# SCH_Fermenter.net
KiCad netlist of a schematic drawn in EasyEDA
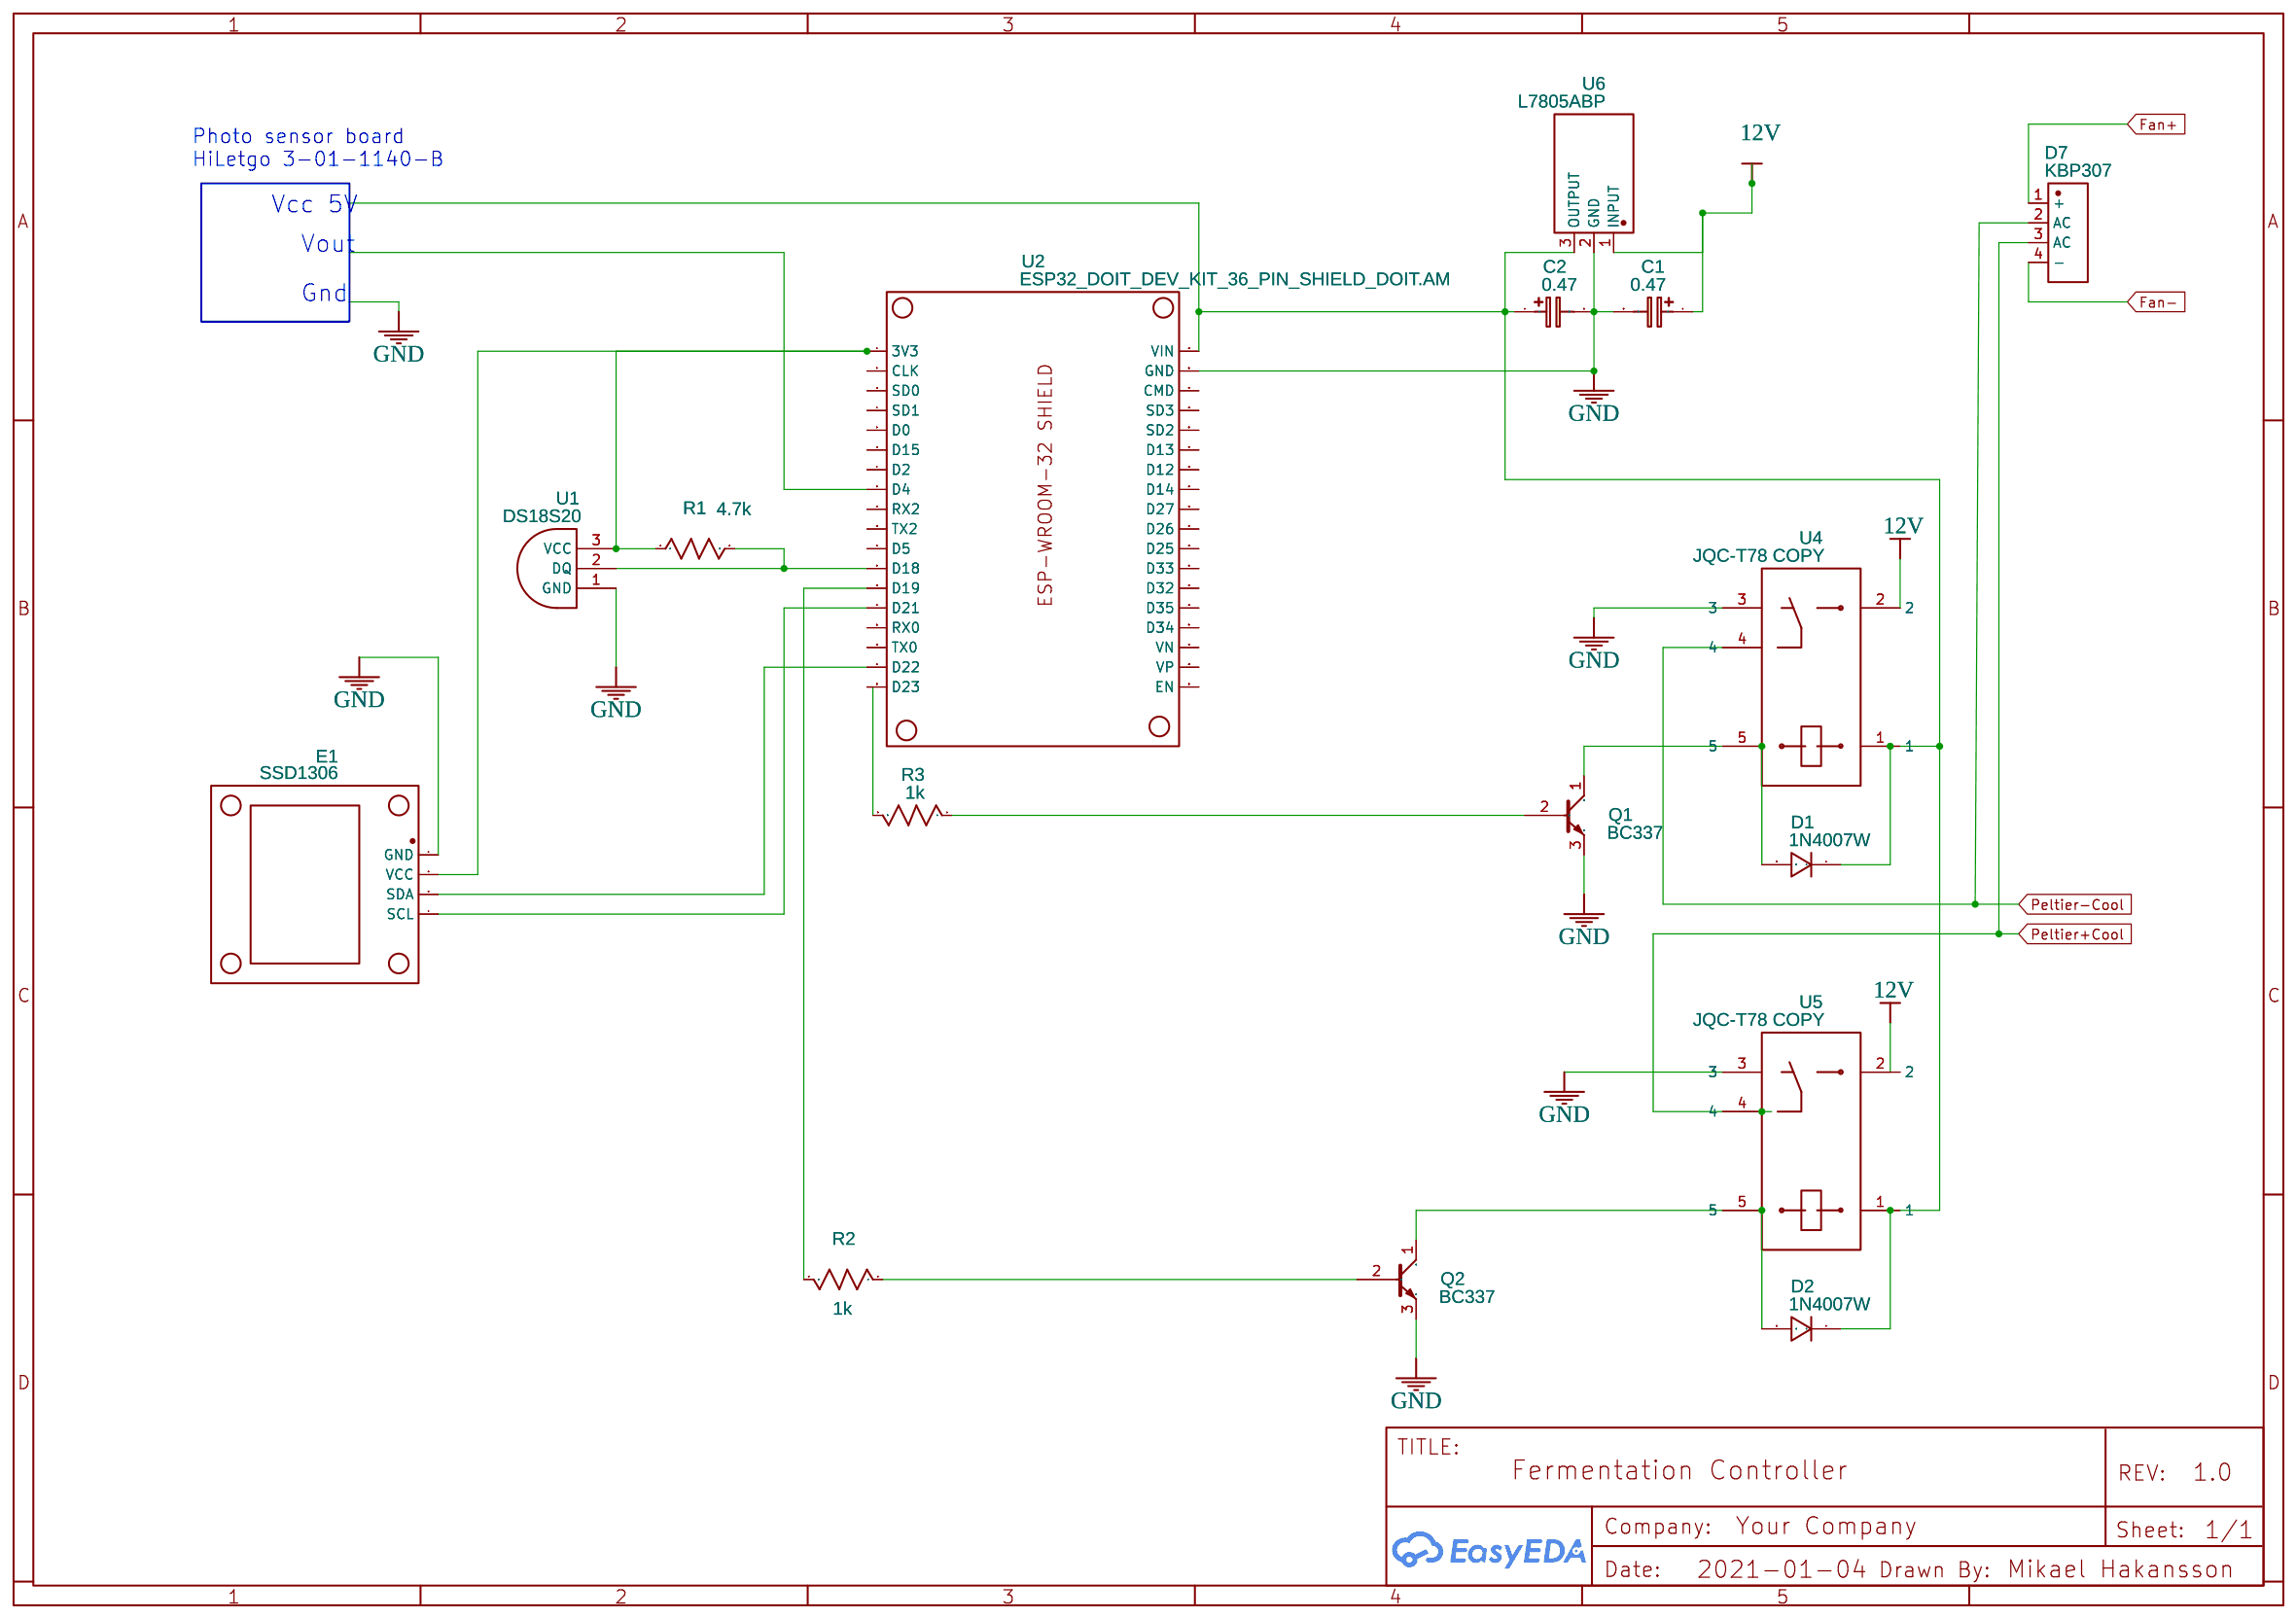
[diagram p0: schematic sheet]

(export (version "E")
  (design (tool "Eeschema 10.0.6"))
  (components
    (comp (ref "C1") (value "0.47") (libsource (lib "") (part "C_Tan_SMD_A_EU")))
    (comp (ref "C2") (value "0.47") (libsource (lib "") (part "C_Tan_SMD_A_EU_1")))
    (comp (ref "D1")
      (value "1N4007W")
      (fields (field (name "Manufacturer") "BLUE ROCKET"))
      (libsource (lib "") (part "1N4007W"))
    )
    (comp (ref "D2")
      (value "1N4007W")
      (fields (field (name "Manufacturer") "BLUE ROCKET"))
      (libsource (lib "") (part "1N4007W"))
    )
    (comp (ref "D7")
      (value "KBP307")
      (fields (field (name "Manufacturer") "MDD"))
      (libsource (lib "") (part "KBP307"))
    )
    (comp (ref "E1")
      (value "SSD1306")
      (fields (field (name "Manufacturer Part") "WJ2EDGVC-5.08-4P") (field (name "Manufacturer") "ReliaPro"))
      (libsource (lib "") (part "SSD1306"))
    )
    (comp (ref "Q1") (value "BC337") (libsource (lib "") (part "BC337")))
    (comp (ref "Q2") (value "BC337") (libsource (lib "") (part "BC337")))
    (comp (ref "R1") (value "4.7k") (libsource (lib "") (part "R_0603_US")))
    (comp (ref "R2") (value "1k") (libsource (lib "") (part "R_0603_US_1")))
    (comp (ref "R3") (value "1k") (libsource (lib "") (part "R_0603_US_1")))
    (comp (ref "U1")
      (value "DS18S20")
      (fields (field (name "Manufacturer") "MAXIM"))
      (libsource (lib "") (part "DS18S20"))
    )
    (comp (ref "U2")
      (value "ESP32_DOIT_DEV_KIT_36_PIN_SHIELD_DOIT.AM")
      (fields (field (name "Manufacturer Part") "ESP32_DOIT_DEVKIT_36_PIN"))
      (libsource (lib "") (part "ESP32_DOIT_DEV_KIT_36_PIN_SHIELD_DOIT.AM"))
    )
    (comp (ref "U4") (value "JQC-T78 COPY") (libsource (lib "") (part "JQC-T78 COPY")))
    (comp (ref "U5") (value "JQC-T78 COPY") (libsource (lib "") (part "JQC-T78 COPY")))
    (comp (ref "U6")
      (value "L7805ABP")
      (fields (field (name "Manufacturer") "ST(意法半导体)"))
      (libsource (lib "") (part "L7805ABP"))
    )
  )
  (nets
    (net (code "1") (name "12V") (class "Default")
      (node (ref "C1") (pin "1") (pinfunction "1_1") (pintype "unspecified"))
      (node (ref "U4") (pin "2") (pinfunction "2_2") (pintype "unspecified"))
      (node (ref "U5") (pin "2") (pinfunction "2_2") (pintype "unspecified"))
      (node (ref "U6") (pin "1") (pinfunction "INPUT_1") (pintype "unspecified"))
    )
    (net (code "2") (name "Fan+") (class "Default")
      (node (ref "D7") (pin "1") (pinfunction "+_1") (pintype "unspecified"))
    )
    (net (code "3") (name "Fan-") (class "Default")
      (node (ref "D7") (pin "4") (pinfunction "-_4") (pintype "unspecified"))
    )
    (net (code "4") (name "GND") (class "Default")
      (node (ref "C1") (pin "2") (pinfunction "2_2") (pintype "unspecified"))
      (node (ref "C2") (pin "2") (pinfunction "2_2") (pintype "unspecified"))
      (node (ref "E1") (pin "1") (pinfunction "GND_1") (pintype "unspecified"))
      (node (ref "Q1") (pin "3") (pinfunction "E_3") (pintype "unspecified"))
      (node (ref "Q2") (pin "3") (pinfunction "E_3") (pintype "unspecified"))
      (node (ref "U1") (pin "1") (pinfunction "GND_1") (pintype "unspecified"))
      (node (ref "U2") (pin "35") (pinfunction "GND_35") (pintype "input"))
      (node (ref "U4") (pin "3") (pinfunction "3_3") (pintype "unspecified"))
      (node (ref "U5") (pin "3") (pinfunction "3_3") (pintype "unspecified"))
      (node (ref "U6") (pin "2") (pinfunction "GND_2") (pintype "unspecified"))
    )
    (net (code "5") (name "Net-(E1-SCL)") (class "Default")
      (node (ref "E1") (pin "4") (pinfunction "SCL_4") (pintype "unspecified"))
      (node (ref "U2") (pin "14") (pinfunction "D21_14") (pintype "input"))
    )
    (net (code "6") (name "Net-(E1-SDA)") (class "Default")
      (node (ref "E1") (pin "3") (pinfunction "SDA_3") (pintype "unspecified"))
      (node (ref "U2") (pin "17") (pinfunction "D22_17") (pintype "input"))
    )
    (net (code "7") (name "Net-(E1-VCC)") (class "Default")
      (node (ref "E1") (pin "2") (pinfunction "VCC_2") (pintype "unspecified"))
      (node (ref "R1") (pin "1") (pinfunction "1_1") (pintype "unspecified"))
      (node (ref "U1") (pin "3") (pinfunction "VCC_3") (pintype "unspecified"))
      (node (ref "U2") (pin "1") (pinfunction "3V3_1") (pintype "input"))
    )
    (net (code "8") (name "Net-(Q1-B)") (class "Default")
      (node (ref "Q1") (pin "2") (pinfunction "B_2") (pintype "input"))
      (node (ref "R3") (pin "1") (pinfunction "1_1") (pintype "unspecified"))
    )
    (net (code "9") (name "Net-(Q1-C)") (class "Default")
      (node (ref "D1") (pin "2") (pinfunction "2_2") (pintype "unspecified"))
      (node (ref "Q1") (pin "1") (pinfunction "C_1") (pintype "unspecified"))
      (node (ref "U4") (pin "5") (pinfunction "5_5") (pintype "unspecified"))
    )
    (net (code "10") (name "Net-(Q2-B)") (class "Default")
      (node (ref "Q2") (pin "2") (pinfunction "B_2") (pintype "input"))
      (node (ref "R2") (pin "1") (pinfunction "1_1") (pintype "unspecified"))
    )
    (net (code "11") (name "Net-(Q2-C)") (class "Default")
      (node (ref "D2") (pin "2") (pinfunction "2_2") (pintype "unspecified"))
      (node (ref "Q2") (pin "1") (pinfunction "C_1") (pintype "unspecified"))
      (node (ref "U5") (pin "5") (pinfunction "5_5") (pintype "unspecified"))
    )
    (net (code "12") (name "Net-(U1-DQ)") (class "Default")
      (node (ref "R1") (pin "2") (pinfunction "2_2") (pintype "unspecified"))
      (node (ref "U1") (pin "2") (pinfunction "DQ_2") (pintype "unspecified"))
      (node (ref "U2") (pin "12") (pinfunction "D18_12") (pintype "input"))
    )
    (net (code "13") (name "Net-(U2-D19)") (class "Default")
      (node (ref "R2") (pin "2") (pinfunction "2_2") (pintype "unspecified"))
      (node (ref "U2") (pin "13") (pinfunction "D19_13") (pintype "input"))
    )
    (net (code "14") (name "Net-(U2-D23)") (class "Default")
      (node (ref "R3") (pin "2") (pinfunction "2_2") (pintype "unspecified"))
      (node (ref "U2") (pin "18") (pinfunction "D23_18") (pintype "input"))
    )
    (net (code "15") (name "Net-(U2-VIN)") (class "Default")
      (node (ref "C2") (pin "1") (pinfunction "1_1") (pintype "unspecified"))
      (node (ref "D1") (pin "1") (pinfunction "1_1") (pintype "unspecified"))
      (node (ref "D2") (pin "1") (pinfunction "1_1") (pintype "unspecified"))
      (node (ref "U2") (pin "36") (pinfunction "VIN_36") (pintype "input"))
      (node (ref "U4") (pin "1") (pinfunction "1_1") (pintype "unspecified"))
      (node (ref "U5") (pin "1") (pinfunction "1_1") (pintype "unspecified"))
      (node (ref "U6") (pin "3") (pinfunction "OUTPUT_3") (pintype "unspecified"))
    )
    (net (code "16") (name "Peltier+Cool") (class "Default")
      (node (ref "D7") (pin "3") (pinfunction "AC_3") (pintype "unspecified"))
      (node (ref "U5") (pin "4") (pinfunction "4_4") (pintype "unspecified"))
    )
    (net (code "17") (name "Peltier-Cool") (class "Default")
      (node (ref "D7") (pin "2") (pinfunction "AC_2") (pintype "unspecified"))
      (node (ref "U4") (pin "4") (pinfunction "4_4") (pintype "unspecified"))
    )
    (net (code "18") (name "unconnected-(U2-CLK-Pad2)") (class "Default")
      (node (ref "U2") (pin "2") (pinfunction "CLK_2") (pintype "input"))
    )
    (net (code "19") (name "unconnected-(U2-CMD-Pad34)") (class "Default")
      (node (ref "U2") (pin "34") (pinfunction "CMD_34") (pintype "input"))
    )
    (net (code "20") (name "unconnected-(U2-D0-Pad5)") (class "Default")
      (node (ref "U2") (pin "5") (pinfunction "D0_5") (pintype "input"))
    )
    (net (code "21") (name "unconnected-(U2-D2-Pad7)") (class "Default")
      (node (ref "U2") (pin "7") (pinfunction "D2_7") (pintype "input"))
    )
    (net (code "22") (name "unconnected-(U2-D4-Pad8)") (class "Default")
      (node (ref "U2") (pin "8") (pinfunction "D4_8") (pintype "input"))
    )
    (net (code "23") (name "unconnected-(U2-D5-Pad11)") (class "Default")
      (node (ref "U2") (pin "11") (pinfunction "D5_11") (pintype "input"))
    )
    (net (code "24") (name "unconnected-(U2-D12-Pad30)") (class "Default")
      (node (ref "U2") (pin "30") (pinfunction "D12_30") (pintype "input"))
    )
    (net (code "25") (name "unconnected-(U2-D13-Pad31)") (class "Default")
      (node (ref "U2") (pin "31") (pinfunction "D13_31") (pintype "input"))
    )
    (net (code "26") (name "unconnected-(U2-D14-Pad29)") (class "Default")
      (node (ref "U2") (pin "29") (pinfunction "D14_29") (pintype "input"))
    )
    (net (code "27") (name "unconnected-(U2-D15-Pad6)") (class "Default")
      (node (ref "U2") (pin "6") (pinfunction "D15_6") (pintype "input"))
    )
    (net (code "28") (name "unconnected-(U2-D25-Pad26)") (class "Default")
      (node (ref "U2") (pin "26") (pinfunction "D25_26") (pintype "input"))
    )
    (net (code "29") (name "unconnected-(U2-D26-Pad27)") (class "Default")
      (node (ref "U2") (pin "27") (pinfunction "D26_27") (pintype "input"))
    )
    (net (code "30") (name "unconnected-(U2-D27-Pad28)") (class "Default")
      (node (ref "U2") (pin "28") (pinfunction "D27_28") (pintype "input"))
    )
    (net (code "31") (name "unconnected-(U2-D32-Pad24)") (class "Default")
      (node (ref "U2") (pin "24") (pinfunction "D32_24") (pintype "input"))
    )
    (net (code "32") (name "unconnected-(U2-D33-Pad25)") (class "Default")
      (node (ref "U2") (pin "25") (pinfunction "D33_25") (pintype "input"))
    )
    (net (code "33") (name "unconnected-(U2-D34-Pad22)") (class "Default")
      (node (ref "U2") (pin "22") (pinfunction "D34_22") (pintype "input"))
    )
    (net (code "34") (name "unconnected-(U2-D35-Pad23)") (class "Default")
      (node (ref "U2") (pin "23") (pinfunction "D35_23") (pintype "input"))
    )
    (net (code "35") (name "unconnected-(U2-EN-Pad19)") (class "Default")
      (node (ref "U2") (pin "19") (pinfunction "EN_19") (pintype "input"))
    )
    (net (code "36") (name "unconnected-(U2-RX0-Pad15)") (class "Default")
      (node (ref "U2") (pin "15") (pinfunction "RX0_15") (pintype "input"))
    )
    (net (code "37") (name "unconnected-(U2-RX2-Pad9)") (class "Default")
      (node (ref "U2") (pin "9") (pinfunction "RX2_9") (pintype "input"))
    )
    (net (code "38") (name "unconnected-(U2-SD0-Pad3)") (class "Default")
      (node (ref "U2") (pin "3") (pinfunction "SD0_3") (pintype "input"))
    )
    (net (code "39") (name "unconnected-(U2-SD1-Pad4)") (class "Default")
      (node (ref "U2") (pin "4") (pinfunction "SD1_4") (pintype "input"))
    )
    (net (code "40") (name "unconnected-(U2-SD2-Pad32)") (class "Default")
      (node (ref "U2") (pin "32") (pinfunction "SD2_32") (pintype "input"))
    )
    (net (code "41") (name "unconnected-(U2-SD3-Pad33)") (class "Default")
      (node (ref "U2") (pin "33") (pinfunction "SD3_33") (pintype "input"))
    )
    (net (code "42") (name "unconnected-(U2-TX0-Pad16)") (class "Default")
      (node (ref "U2") (pin "16") (pinfunction "TX0_16") (pintype "input"))
    )
    (net (code "43") (name "unconnected-(U2-TX2-Pad10)") (class "Default")
      (node (ref "U2") (pin "10") (pinfunction "TX2_10") (pintype "input"))
    )
    (net (code "44") (name "unconnected-(U2-VN-Pad21)") (class "Default")
      (node (ref "U2") (pin "21") (pinfunction "VN_21") (pintype "input"))
    )
    (net (code "45") (name "unconnected-(U2-VP-Pad20)") (class "Default")
      (node (ref "U2") (pin "20") (pinfunction "VP_20") (pintype "input"))
    )
  )
)
